# TC_TP2_EJ6.net
KiCad netlist of a schematic drawn in Altium Designer
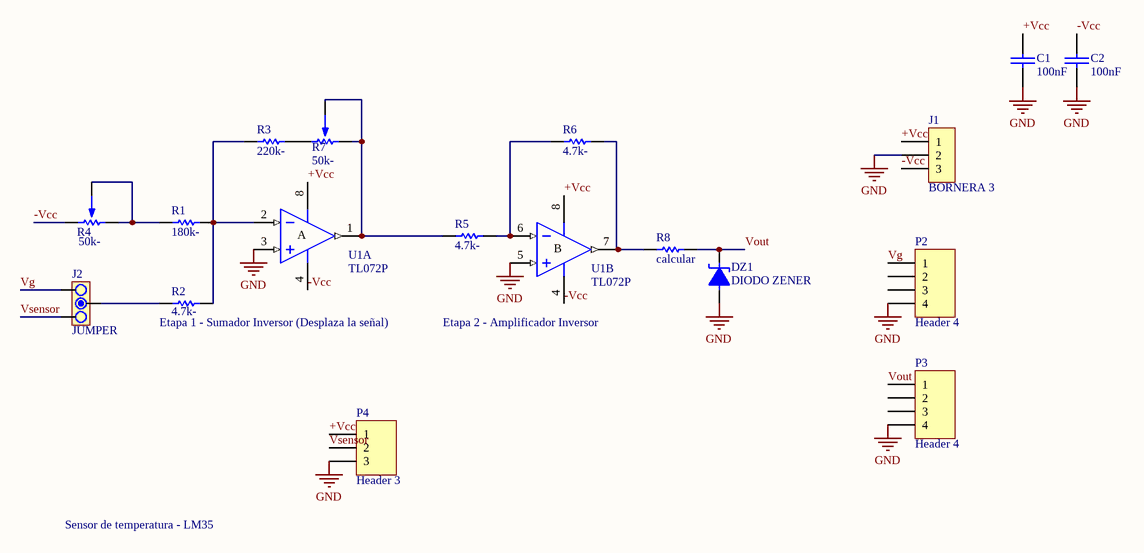
[diagram p0: TC_TP2_EJ6.SchDoc]

(export (version "E")
  (design (tool "Eeschema 10.0.6"))
  (components
    (comp (ref "C1") (value "100nF") (footprint "CAP200") (libsource (lib "LIBEBAL") (part "CAP")))
    (comp (ref "C2") (value "100nF") (footprint "CAP200") (libsource (lib "LIBEBAL") (part "CAP")))
    (comp (ref "DZ1")
      (value "DIODO ZENER")
      (footprint "DO41")
      (libsource (lib "LIBEBAL") (part "DIODO ZENER"))
    )
    (comp (ref "J1")
      (value "BORNERA 3")
      (footprint "BORNERA3")
      (libsource (lib "LIBEBAL") (part "BORNERA 3"))
    )
    (comp (ref "J2") (value "JUMPER") (footprint "JUMPER3") (libsource (lib "LIBEBAL") (part "JUMPER3")))
    (comp (ref "P2")
      (value "Header 4")
      (footprint "HDR1X4")
      (description "Header, 4-Pin")
      (fields (field (name "PUBLISHER") "Altium Limited"))
      (libsource (lib "Miscellaneous Connectors") (part "Header 4"))
    )
    (comp (ref "P3")
      (value "Header 4")
      (footprint "HDR1X4")
      (description "Header, 4-Pin")
      (fields (field (name "PUBLISHER") "Altium Limited"))
      (libsource (lib "Miscellaneous Connectors") (part "Header 4"))
    )
    (comp (ref "P4")
      (value "Header 3")
      (footprint "HDR1X3")
      (description "Header, 3-Pin")
      (fields (field (name "PUBLISHER") "Altium Limited"))
      (libsource (lib "Miscellaneous Connectors") (part "Header 3"))
    )
    (comp (ref "R1") (value "180k-") (footprint "RES400") (libsource (lib "LIBEBAL") (part "RES")))
    (comp (ref "R2") (value "4.7k-") (footprint "RES400") (libsource (lib "LIBEBAL") (part "RES")))
    (comp (ref "R3") (value "220k-") (footprint "RES400") (libsource (lib "LIBEBAL") (part "RES")))
    (comp (ref "R4") (value "50k-") (footprint "PRESET V") (libsource (lib "LIBEBAL") (part "PRESET")))
    (comp (ref "R5") (value "4.7k-") (footprint "RES400") (libsource (lib "LIBEBAL") (part "RES")))
    (comp (ref "R6") (value "4.7k-") (footprint "RES400") (libsource (lib "LIBEBAL") (part "RES")))
    (comp (ref "R7") (value "50k-") (footprint "PRESET V") (libsource (lib "LIBEBAL") (part "PRESET")))
    (comp (ref "R8") (value "calcular") (footprint "RES400") (libsource (lib "LIBEBAL") (part "RES")))
    (comp (ref "U1")
      (value "TL072P")
      (footprint "P008")
      (description "Low-Noise JFET-Input Operational Amplifier")
      (fields (field (name "PUBLISHER") "Altium Limited"))
      (libsource (lib "TI Operational Amplifier") (part "TL072P"))
    )
  )
  (nets
    (net (code "1") (name "/+Vcc") (class "Default")
      (node (ref "C1") (pin "1") (pinfunction "1_1") (pintype "passive"))
      (node (ref "J1") (pin "1") (pinfunction "1_1") (pintype "passive"))
      (node (ref "P4") (pin "1") (pinfunction "1_1") (pintype "passive"))
      (node (ref "U1") (pin "8") (pinfunction "V+_8") (pintype "power_in"))
    )
    (net (code "2") (name "/-Vcc") (class "Default")
      (node (ref "C2") (pin "1") (pinfunction "1_1") (pintype "passive"))
      (node (ref "J1") (pin "3") (pinfunction "3_3") (pintype "passive"))
      (node (ref "R4") (pin "1") (pinfunction "1_1") (pintype "passive"))
      (node (ref "U1") (pin "4") (pinfunction "V-_4") (pintype "power_in"))
    )
    (net (code "3") (name "/Vg") (class "Default")
      (node (ref "J2") (pin "3") (pinfunction "3_3") (pintype "passive"))
      (node (ref "P2") (pin "1") (pinfunction "1_1") (pintype "passive"))
    )
    (net (code "4") (name "/Vout") (class "Default")
      (node (ref "DZ1") (pin "2") (pinfunction "2_2") (pintype "passive"))
      (node (ref "P3") (pin "1") (pinfunction "1_1") (pintype "passive"))
      (node (ref "R8") (pin "2") (pinfunction "2_2") (pintype "passive"))
    )
    (net (code "5") (name "/Vsensor") (class "Default")
      (node (ref "J2") (pin "1") (pinfunction "1_1") (pintype "passive"))
      (node (ref "P4") (pin "2") (pinfunction "2_2") (pintype "passive"))
    )
    (net (code "6") (name "GND") (class "Default")
      (node (ref "C1") (pin "2") (pinfunction "2_2") (pintype "passive"))
      (node (ref "C2") (pin "2") (pinfunction "2_2") (pintype "passive"))
      (node (ref "DZ1") (pin "1") (pinfunction "1_1") (pintype "passive"))
      (node (ref "J1") (pin "2") (pinfunction "2_2") (pintype "passive"))
      (node (ref "P2") (pin "4") (pinfunction "4_4") (pintype "passive"))
      (node (ref "P3") (pin "4") (pinfunction "4_4") (pintype "passive"))
      (node (ref "P4") (pin "3") (pinfunction "3_3") (pintype "passive"))
      (node (ref "U1") (pin "3") (pinfunction "IN+_3") (pintype "input"))
      (node (ref "U1") (pin "5") (pinfunction "IN+_5") (pintype "input"))
    )
    (net (code "7") (name "Net-(J2-Pad2)") (class "Default")
      (node (ref "J2") (pin "2") (pinfunction "2_2") (pintype "passive"))
      (node (ref "R2") (pin "1") (pinfunction "1_1") (pintype "passive"))
    )
    (net (code "8") (name "Net-(R1-Pad1)") (class "Default")
      (node (ref "R1") (pin "1") (pinfunction "1_1") (pintype "passive"))
      (node (ref "R4") (pin "2") (pinfunction "2_2") (pintype "passive"))
      (node (ref "R4") (pin "3") (pinfunction "3_3") (pintype "passive"))
    )
    (net (code "9") (name "Net-(R3-Pad2)") (class "Default")
      (node (ref "R3") (pin "2") (pinfunction "2_2") (pintype "passive"))
      (node (ref "R7") (pin "1") (pinfunction "1_1") (pintype "passive"))
    )
    (net (code "10") (name "Net-(U1A-IN-)") (class "Default")
      (node (ref "R1") (pin "2") (pinfunction "2_2") (pintype "passive"))
      (node (ref "R2") (pin "2") (pinfunction "2_2") (pintype "passive"))
      (node (ref "R3") (pin "1") (pinfunction "1_1") (pintype "passive"))
      (node (ref "U1") (pin "2") (pinfunction "IN-_2") (pintype "input"))
    )
    (net (code "11") (name "Net-(U1A-OUT)") (class "Default")
      (node (ref "R5") (pin "1") (pinfunction "1_1") (pintype "passive"))
      (node (ref "R7") (pin "2") (pinfunction "2_2") (pintype "passive"))
      (node (ref "R7") (pin "3") (pinfunction "3_3") (pintype "passive"))
      (node (ref "U1") (pin "1") (pinfunction "OUT_1") (pintype "output"))
    )
    (net (code "12") (name "Net-(U1B-IN-)") (class "Default")
      (node (ref "R5") (pin "2") (pinfunction "2_2") (pintype "passive"))
      (node (ref "R6") (pin "1") (pinfunction "1_1") (pintype "passive"))
      (node (ref "U1") (pin "6") (pinfunction "IN-_6") (pintype "input"))
    )
    (net (code "13") (name "Net-(U1B-OUT)") (class "Default")
      (node (ref "R6") (pin "2") (pinfunction "2_2") (pintype "passive"))
      (node (ref "R8") (pin "1") (pinfunction "1_1") (pintype "passive"))
      (node (ref "U1") (pin "7") (pinfunction "OUT_7") (pintype "output"))
    )
    (net (code "14") (name "unconnected-(P2-Pad2)") (class "Default")
      (node (ref "P2") (pin "2") (pinfunction "2_2") (pintype "passive"))
    )
    (net (code "15") (name "unconnected-(P2-Pad3)") (class "Default")
      (node (ref "P2") (pin "3") (pinfunction "3_3") (pintype "passive"))
    )
    (net (code "16") (name "unconnected-(P3-Pad2)") (class "Default")
      (node (ref "P3") (pin "2") (pinfunction "2_2") (pintype "passive"))
    )
    (net (code "17") (name "unconnected-(P3-Pad3)") (class "Default")
      (node (ref "P3") (pin "3") (pinfunction "3_3") (pintype "passive"))
    )
  )
)
